# lh.net
KiCad netlist of a schematic drawn in EAGLE
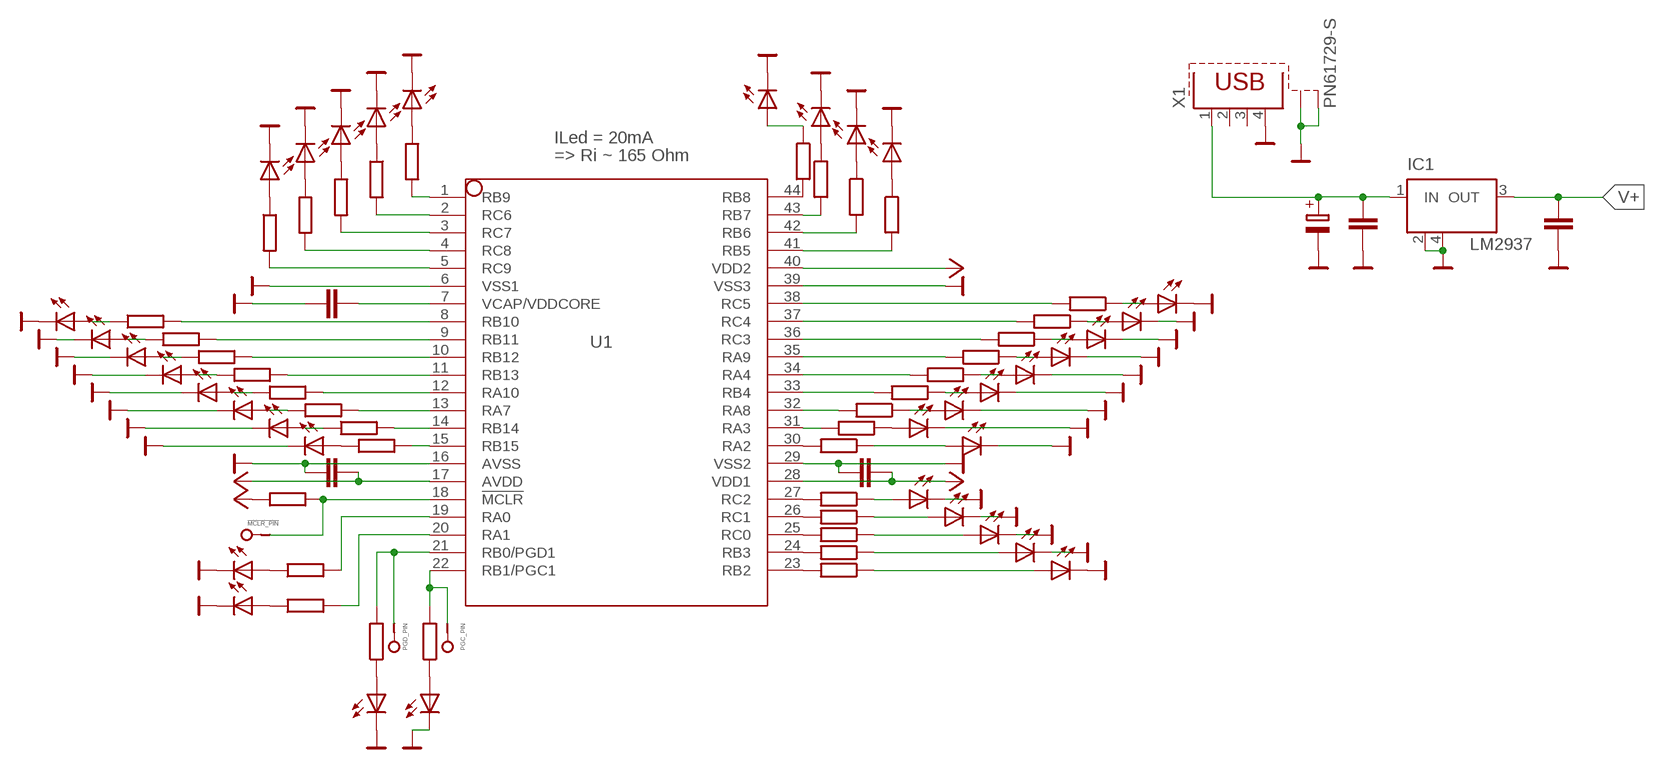
[diagram p0: schematic, sheet 1]

(export (version "E")
  (design (tool "Eeschema 10.0.6"))
  (components
    (comp (ref "!MCLR_PIN")
      (value "1_PIN_CONPLANAR")
      (footprint "eagle-import:1_PIN_PLANAR")
      (libsource (lib "eagle-import") (part "1_PIN_CONPLANAR"))
    )
    (comp (ref "C1")
      (value "SMD_CAPC0805K")
      (footprint "eagle-import:C0805K")
      (libsource (lib "eagle-import") (part "SMD_CAPC0805K"))
    )
    (comp (ref "C2")
      (value "SMD_CAPC0805K")
      (footprint "eagle-import:C0805K")
      (libsource (lib "eagle-import") (part "SMD_CAPC0805K"))
    )
    (comp (ref "C3")
      (value "SMD_CAPC0805K")
      (footprint "eagle-import:C0805K")
      (libsource (lib "eagle-import") (part "SMD_CAPC0805K"))
    )
    (comp (ref "C5")
      (value "SMD_CAPC0805K")
      (footprint "eagle-import:C0805K")
      (libsource (lib "eagle-import") (part "SMD_CAPC0805K"))
    )
    (comp (ref "C6")
      (value "SMD_CAPC0805K")
      (footprint "eagle-import:C0805K")
      (libsource (lib "eagle-import") (part "SMD_CAPC0805K"))
    )
    (comp (ref "C7")
      (value "SMD_EL_CAP")
      (footprint "eagle-import:153CLV-0405")
      (libsource (lib "eagle-import") (part "SMD_EL_CAP"))
    )
    (comp (ref "IC1")
      (value "LM2937")
      (footprint "eagle-import:SOT223")
      (libsource (lib "eagle-import") (part "LM2937"))
    )
    (comp (ref "LED1")
      (value "LEDSMT1206")
      (footprint "eagle-import:1206")
      (libsource (lib "eagle-import") (part "LEDSMT1206"))
    )
    (comp (ref "LED2")
      (value "LEDSMT1206")
      (footprint "eagle-import:1206")
      (libsource (lib "eagle-import") (part "LEDSMT1206"))
    )
    (comp (ref "LED3")
      (value "LEDSMT1206")
      (footprint "eagle-import:1206")
      (libsource (lib "eagle-import") (part "LEDSMT1206"))
    )
    (comp (ref "LED4")
      (value "LEDSMT1206")
      (footprint "eagle-import:1206")
      (libsource (lib "eagle-import") (part "LEDSMT1206"))
    )
    (comp (ref "LED5")
      (value "LEDSMT1206")
      (footprint "eagle-import:1206")
      (libsource (lib "eagle-import") (part "LEDSMT1206"))
    )
    (comp (ref "LED6")
      (value "LEDSMT1206")
      (footprint "eagle-import:1206")
      (libsource (lib "eagle-import") (part "LEDSMT1206"))
    )
    (comp (ref "LED7")
      (value "LEDSMT1206")
      (footprint "eagle-import:1206")
      (libsource (lib "eagle-import") (part "LEDSMT1206"))
    )
    (comp (ref "LED8")
      (value "LEDSMT1206")
      (footprint "eagle-import:1206")
      (libsource (lib "eagle-import") (part "LEDSMT1206"))
    )
    (comp (ref "LED9")
      (value "LEDSMT1206")
      (footprint "eagle-import:1206")
      (libsource (lib "eagle-import") (part "LEDSMT1206"))
    )
    (comp (ref "LED10")
      (value "LEDSMT1206")
      (footprint "eagle-import:1206")
      (libsource (lib "eagle-import") (part "LEDSMT1206"))
    )
    (comp (ref "LED11")
      (value "LEDSMT1206")
      (footprint "eagle-import:1206")
      (libsource (lib "eagle-import") (part "LEDSMT1206"))
    )
    (comp (ref "LED12")
      (value "LEDSMT1206")
      (footprint "eagle-import:1206")
      (libsource (lib "eagle-import") (part "LEDSMT1206"))
    )
    (comp (ref "LED13")
      (value "LEDSMT1206")
      (footprint "eagle-import:1206")
      (libsource (lib "eagle-import") (part "LEDSMT1206"))
    )
    (comp (ref "LED14")
      (value "LEDSMT1206")
      (footprint "eagle-import:1206")
      (libsource (lib "eagle-import") (part "LEDSMT1206"))
    )
    (comp (ref "LED15")
      (value "LEDSMT1206")
      (footprint "eagle-import:1206")
      (libsource (lib "eagle-import") (part "LEDSMT1206"))
    )
    (comp (ref "LED16")
      (value "LEDSMT1206")
      (footprint "eagle-import:1206")
      (libsource (lib "eagle-import") (part "LEDSMT1206"))
    )
    (comp (ref "LED17")
      (value "LEDSMT1206")
      (footprint "eagle-import:1206")
      (libsource (lib "eagle-import") (part "LEDSMT1206"))
    )
    (comp (ref "LED18")
      (value "LEDSMT1206")
      (footprint "eagle-import:1206")
      (libsource (lib "eagle-import") (part "LEDSMT1206"))
    )
    (comp (ref "LED19")
      (value "LEDSMT1206")
      (footprint "eagle-import:1206")
      (libsource (lib "eagle-import") (part "LEDSMT1206"))
    )
    (comp (ref "LED20")
      (value "LEDSMT1206")
      (footprint "eagle-import:1206")
      (libsource (lib "eagle-import") (part "LEDSMT1206"))
    )
    (comp (ref "LED21")
      (value "LEDSMT1206")
      (footprint "eagle-import:1206")
      (libsource (lib "eagle-import") (part "LEDSMT1206"))
    )
    (comp (ref "LED22")
      (value "LEDSMT1206")
      (footprint "eagle-import:1206")
      (libsource (lib "eagle-import") (part "LEDSMT1206"))
    )
    (comp (ref "LED23")
      (value "LEDSMT1206")
      (footprint "eagle-import:1206")
      (libsource (lib "eagle-import") (part "LEDSMT1206"))
    )
    (comp (ref "LED24")
      (value "LEDSMT1206")
      (footprint "eagle-import:1206")
      (libsource (lib "eagle-import") (part "LEDSMT1206"))
    )
    (comp (ref "LED25")
      (value "LEDSMT1206")
      (footprint "eagle-import:1206")
      (libsource (lib "eagle-import") (part "LEDSMT1206"))
    )
    (comp (ref "LED26")
      (value "LEDSMT1206")
      (footprint "eagle-import:1206")
      (libsource (lib "eagle-import") (part "LEDSMT1206"))
    )
    (comp (ref "LED27")
      (value "LEDSMT1206")
      (footprint "eagle-import:1206")
      (libsource (lib "eagle-import") (part "LEDSMT1206"))
    )
    (comp (ref "LED28")
      (value "LEDSMT1206")
      (footprint "eagle-import:1206")
      (libsource (lib "eagle-import") (part "LEDSMT1206"))
    )
    (comp (ref "LED29")
      (value "LEDSMT1206")
      (footprint "eagle-import:1206")
      (libsource (lib "eagle-import") (part "LEDSMT1206"))
    )
    (comp (ref "LED30")
      (value "LEDSMT1206")
      (footprint "eagle-import:1206")
      (libsource (lib "eagle-import") (part "LEDSMT1206"))
    )
    (comp (ref "LED31")
      (value "LEDSMT1206")
      (footprint "eagle-import:1206")
      (libsource (lib "eagle-import") (part "LEDSMT1206"))
    )
    (comp (ref "LED32")
      (value "LEDSMT1206")
      (footprint "eagle-import:1206")
      (libsource (lib "eagle-import") (part "LEDSMT1206"))
    )
    (comp (ref "LED33")
      (value "LEDSMT1206")
      (footprint "eagle-import:1206")
      (libsource (lib "eagle-import") (part "LEDSMT1206"))
    )
    (comp (ref "LED34")
      (value "LEDSMT1206")
      (footprint "eagle-import:1206")
      (libsource (lib "eagle-import") (part "LEDSMT1206"))
    )
    (comp (ref "LED35")
      (value "LEDSMT1206")
      (footprint "eagle-import:1206")
      (libsource (lib "eagle-import") (part "LEDSMT1206"))
    )
    (comp (ref "PGC_PIN")
      (value "1_PIN_CONPLANAR")
      (footprint "eagle-import:1_PIN_PLANAR")
      (libsource (lib "eagle-import") (part "1_PIN_CONPLANAR"))
    )
    (comp (ref "PGD_PIN")
      (value "1_PIN_CONPLANAR")
      (footprint "eagle-import:1_PIN_PLANAR")
      (libsource (lib "eagle-import") (part "1_PIN_CONPLANAR"))
    )
    (comp (ref "R1")
      (value "SMD_RES")
      (footprint "eagle-import:R1206")
      (libsource (lib "eagle-import") (part "SMD_RES"))
    )
    (comp (ref "R2")
      (value "SMD_RES")
      (footprint "eagle-import:R1206")
      (libsource (lib "eagle-import") (part "SMD_RES"))
    )
    (comp (ref "R3")
      (value "SMD_RES")
      (footprint "eagle-import:R1206")
      (libsource (lib "eagle-import") (part "SMD_RES"))
    )
    (comp (ref "R4")
      (value "SMD_RES")
      (footprint "eagle-import:R1206")
      (libsource (lib "eagle-import") (part "SMD_RES"))
    )
    (comp (ref "R5")
      (value "SMD_RES")
      (footprint "eagle-import:R1206")
      (libsource (lib "eagle-import") (part "SMD_RES"))
    )
    (comp (ref "R6")
      (value "SMD_RES")
      (footprint "eagle-import:R1206")
      (libsource (lib "eagle-import") (part "SMD_RES"))
    )
    (comp (ref "R7")
      (value "SMD_RES")
      (footprint "eagle-import:R1206")
      (libsource (lib "eagle-import") (part "SMD_RES"))
    )
    (comp (ref "R8")
      (value "SMD_RES")
      (footprint "eagle-import:R1206")
      (libsource (lib "eagle-import") (part "SMD_RES"))
    )
    (comp (ref "R9")
      (value "SMD_RES")
      (footprint "eagle-import:R1206")
      (libsource (lib "eagle-import") (part "SMD_RES"))
    )
    (comp (ref "R10")
      (value "SMD_RES")
      (footprint "eagle-import:R1206")
      (libsource (lib "eagle-import") (part "SMD_RES"))
    )
    (comp (ref "R11")
      (value "SMD_RES")
      (footprint "eagle-import:R1206")
      (libsource (lib "eagle-import") (part "SMD_RES"))
    )
    (comp (ref "R12")
      (value "SMD_RES")
      (footprint "eagle-import:R1206")
      (libsource (lib "eagle-import") (part "SMD_RES"))
    )
    (comp (ref "R13")
      (value "SMD_RES")
      (footprint "eagle-import:R1206")
      (libsource (lib "eagle-import") (part "SMD_RES"))
    )
    (comp (ref "R14")
      (value "SMD_RES")
      (footprint "eagle-import:R1206")
      (libsource (lib "eagle-import") (part "SMD_RES"))
    )
    (comp (ref "R15")
      (value "SMD_RES")
      (footprint "eagle-import:R1206")
      (libsource (lib "eagle-import") (part "SMD_RES"))
    )
    (comp (ref "R16")
      (value "SMD_RES")
      (footprint "eagle-import:R1206")
      (libsource (lib "eagle-import") (part "SMD_RES"))
    )
    (comp (ref "R17")
      (value "SMD_RES")
      (footprint "eagle-import:R1206")
      (libsource (lib "eagle-import") (part "SMD_RES"))
    )
    (comp (ref "R18")
      (value "SMD_RES")
      (footprint "eagle-import:R1206")
      (libsource (lib "eagle-import") (part "SMD_RES"))
    )
    (comp (ref "R19")
      (value "SMD_RES")
      (footprint "eagle-import:R1206")
      (libsource (lib "eagle-import") (part "SMD_RES"))
    )
    (comp (ref "R20")
      (value "SMD_RES")
      (footprint "eagle-import:R1206")
      (libsource (lib "eagle-import") (part "SMD_RES"))
    )
    (comp (ref "R21")
      (value "SMD_RES")
      (footprint "eagle-import:R1206")
      (libsource (lib "eagle-import") (part "SMD_RES"))
    )
    (comp (ref "R22")
      (value "SMD_RES")
      (footprint "eagle-import:R1206")
      (libsource (lib "eagle-import") (part "SMD_RES"))
    )
    (comp (ref "R23")
      (value "SMD_RES")
      (footprint "eagle-import:R1206")
      (libsource (lib "eagle-import") (part "SMD_RES"))
    )
    (comp (ref "R24")
      (value "SMD_RES")
      (footprint "eagle-import:R1206")
      (libsource (lib "eagle-import") (part "SMD_RES"))
    )
    (comp (ref "R25")
      (value "SMD_RES")
      (footprint "eagle-import:R1206")
      (libsource (lib "eagle-import") (part "SMD_RES"))
    )
    (comp (ref "R26")
      (value "SMD_RES")
      (footprint "eagle-import:R1206")
      (libsource (lib "eagle-import") (part "SMD_RES"))
    )
    (comp (ref "R27")
      (value "SMD_RES")
      (footprint "eagle-import:R1206")
      (libsource (lib "eagle-import") (part "SMD_RES"))
    )
    (comp (ref "R28")
      (value "SMD_RES")
      (footprint "eagle-import:R1206")
      (libsource (lib "eagle-import") (part "SMD_RES"))
    )
    (comp (ref "R29")
      (value "SMD_RES")
      (footprint "eagle-import:R1206")
      (libsource (lib "eagle-import") (part "SMD_RES"))
    )
    (comp (ref "R30")
      (value "SMD_RES")
      (footprint "eagle-import:R1206")
      (libsource (lib "eagle-import") (part "SMD_RES"))
    )
    (comp (ref "R31")
      (value "SMD_RES")
      (footprint "eagle-import:R1206")
      (libsource (lib "eagle-import") (part "SMD_RES"))
    )
    (comp (ref "R32")
      (value "SMD_RES")
      (footprint "eagle-import:R1206")
      (libsource (lib "eagle-import") (part "SMD_RES"))
    )
    (comp (ref "R33")
      (value "SMD_RES")
      (footprint "eagle-import:R1206")
      (libsource (lib "eagle-import") (part "SMD_RES"))
    )
    (comp (ref "R34")
      (value "SMD_RES")
      (footprint "eagle-import:R1206")
      (libsource (lib "eagle-import") (part "SMD_RES"))
    )
    (comp (ref "R35")
      (value "SMD_RES")
      (footprint "eagle-import:R1206")
      (libsource (lib "eagle-import") (part "SMD_RES"))
    )
    (comp (ref "R36")
      (value "SMD_RES")
      (footprint "eagle-import:R1206")
      (libsource (lib "eagle-import") (part "SMD_RES"))
    )
    (comp (ref "U1")
      (value "DSPIC33FJ64GP204")
      (footprint "eagle-import:TQFP44")
      (libsource (lib "eagle-import") (part "DSPIC33FJ64GP204"))
    )
    (comp (ref "X1")
      (value "PN61729-S")
      (footprint "eagle-import:PN61729-S")
      (libsource (lib "eagle-import") (part "PN61729-S"))
    )
  )
  (nets
    (net (code "1") (name "0V") (class "Default")
      (node (ref "C1") (pin "2") (pinfunction "2_2") (pintype "passive"))
      (node (ref "C2") (pin "2") (pinfunction "2_2") (pintype "passive"))
      (node (ref "C3") (pin "1") (pinfunction "1_1") (pintype "passive"))
      (node (ref "C5") (pin "2") (pinfunction "2_2") (pintype "passive"))
      (node (ref "C6") (pin "2") (pinfunction "2_2") (pintype "passive"))
      (node (ref "C7") (pin "-") (pinfunction "P$2_-") (pintype "bidirectional"))
      (node (ref "IC1") (pin "2") (pinfunction "GND_2") (pintype "power_in"))
      (node (ref "IC1") (pin "4") (pinfunction "GND_4") (pintype "power_in"))
      (node (ref "LED1") (pin "C") (pinfunction "C_C") (pintype "passive"))
      (node (ref "LED10") (pin "C") (pinfunction "C_C") (pintype "passive"))
      (node (ref "LED11") (pin "C") (pinfunction "C_C") (pintype "passive"))
      (node (ref "LED12") (pin "C") (pinfunction "C_C") (pintype "passive"))
      (node (ref "LED13") (pin "C") (pinfunction "C_C") (pintype "passive"))
      (node (ref "LED14") (pin "C") (pinfunction "C_C") (pintype "passive"))
      (node (ref "LED15") (pin "C") (pinfunction "C_C") (pintype "passive"))
      (node (ref "LED16") (pin "C") (pinfunction "C_C") (pintype "passive"))
      (node (ref "LED17") (pin "C") (pinfunction "C_C") (pintype "passive"))
      (node (ref "LED18") (pin "C") (pinfunction "C_C") (pintype "passive"))
      (node (ref "LED19") (pin "C") (pinfunction "C_C") (pintype "passive"))
      (node (ref "LED2") (pin "C") (pinfunction "C_C") (pintype "passive"))
      (node (ref "LED20") (pin "C") (pinfunction "C_C") (pintype "passive"))
      (node (ref "LED21") (pin "C") (pinfunction "C_C") (pintype "passive"))
      (node (ref "LED22") (pin "C") (pinfunction "C_C") (pintype "passive"))
      (node (ref "LED23") (pin "C") (pinfunction "C_C") (pintype "passive"))
      (node (ref "LED24") (pin "C") (pinfunction "C_C") (pintype "passive"))
      (node (ref "LED25") (pin "C") (pinfunction "C_C") (pintype "passive"))
      (node (ref "LED26") (pin "C") (pinfunction "C_C") (pintype "passive"))
      (node (ref "LED27") (pin "C") (pinfunction "C_C") (pintype "passive"))
      (node (ref "LED28") (pin "C") (pinfunction "C_C") (pintype "passive"))
      (node (ref "LED29") (pin "C") (pinfunction "C_C") (pintype "passive"))
      (node (ref "LED3") (pin "C") (pinfunction "C_C") (pintype "passive"))
      (node (ref "LED30") (pin "C") (pinfunction "C_C") (pintype "passive"))
      (node (ref "LED31") (pin "C") (pinfunction "C_C") (pintype "passive"))
      (node (ref "LED32") (pin "C") (pinfunction "C_C") (pintype "passive"))
      (node (ref "LED33") (pin "C") (pinfunction "C_C") (pintype "passive"))
      (node (ref "LED34") (pin "C") (pinfunction "C_C") (pintype "passive"))
      (node (ref "LED35") (pin "C") (pinfunction "C_C") (pintype "passive"))
      (node (ref "LED4") (pin "C") (pinfunction "C_C") (pintype "passive"))
      (node (ref "LED5") (pin "C") (pinfunction "C_C") (pintype "passive"))
      (node (ref "LED6") (pin "C") (pinfunction "C_C") (pintype "passive"))
      (node (ref "LED7") (pin "C") (pinfunction "C_C") (pintype "passive"))
      (node (ref "LED8") (pin "C") (pinfunction "C_C") (pintype "passive"))
      (node (ref "LED9") (pin "C") (pinfunction "C_C") (pintype "passive"))
      (node (ref "U1") (pin "16") (pinfunction "AVSS_16") (pintype "bidirectional"))
      (node (ref "U1") (pin "29") (pinfunction "VSS2_29") (pintype "bidirectional"))
      (node (ref "U1") (pin "39") (pinfunction "VSS3_39") (pintype "bidirectional"))
      (node (ref "U1") (pin "6") (pinfunction "VSS1_6") (pintype "bidirectional"))
      (node (ref "X1") (pin "4") (pinfunction "4_4") (pintype "passive"))
      (node (ref "X1") (pin "S1") (pinfunction "S1_S1") (pintype "passive"))
      (node (ref "X1") (pin "S2") (pinfunction "S2_S2") (pintype "passive"))
    )
    (net (code "2") (name "Net-(C7-P$1)") (class "Default")
      (node (ref "C2") (pin "1") (pinfunction "1_1") (pintype "passive"))
      (node (ref "C7") (pin "+") (pinfunction "P$1_+") (pintype "bidirectional"))
      (node (ref "IC1") (pin "1") (pinfunction "IN_1") (pintype "input"))
      (node (ref "X1") (pin "1") (pinfunction "1_1") (pintype "passive"))
    )
    (net (code "3") (name "Net-(LED1-PadA)") (class "Default")
      (node (ref "LED1") (pin "A") (pinfunction "A_A") (pintype "passive"))
      (node (ref "R1") (pin "1") (pinfunction "1_1") (pintype "passive"))
    )
    (net (code "4") (name "Net-(LED2-PadA)") (class "Default")
      (node (ref "LED2") (pin "A") (pinfunction "A_A") (pintype "passive"))
      (node (ref "R2") (pin "1") (pinfunction "1_1") (pintype "passive"))
    )
    (net (code "5") (name "Net-(LED3-PadA)") (class "Default")
      (node (ref "LED3") (pin "A") (pinfunction "A_A") (pintype "passive"))
      (node (ref "R3") (pin "1") (pinfunction "1_1") (pintype "passive"))
    )
    (net (code "6") (name "Net-(LED4-PadA)") (class "Default")
      (node (ref "LED4") (pin "A") (pinfunction "A_A") (pintype "passive"))
      (node (ref "R4") (pin "1") (pinfunction "1_1") (pintype "passive"))
    )
    (net (code "7") (name "Net-(LED5-PadA)") (class "Default")
      (node (ref "LED5") (pin "A") (pinfunction "A_A") (pintype "passive"))
      (node (ref "R5") (pin "1") (pinfunction "1_1") (pintype "passive"))
    )
    (net (code "8") (name "Net-(LED6-PadA)") (class "Default")
      (node (ref "LED6") (pin "A") (pinfunction "A_A") (pintype "passive"))
      (node (ref "R6") (pin "1") (pinfunction "1_1") (pintype "passive"))
    )
    (net (code "9") (name "Net-(LED7-PadA)") (class "Default")
      (node (ref "LED7") (pin "A") (pinfunction "A_A") (pintype "passive"))
      (node (ref "R13") (pin "1") (pinfunction "1_1") (pintype "passive"))
    )
    (net (code "10") (name "Net-(LED8-PadA)") (class "Default")
      (node (ref "LED8") (pin "A") (pinfunction "A_A") (pintype "passive"))
      (node (ref "R14") (pin "1") (pinfunction "1_1") (pintype "passive"))
    )
    (net (code "11") (name "Net-(LED9-PadA)") (class "Default")
      (node (ref "LED9") (pin "A") (pinfunction "A_A") (pintype "passive"))
      (node (ref "R12") (pin "1") (pinfunction "1_1") (pintype "passive"))
    )
    (net (code "12") (name "Net-(LED10-PadA)") (class "Default")
      (node (ref "LED10") (pin "A") (pinfunction "A_A") (pintype "passive"))
      (node (ref "R11") (pin "1") (pinfunction "1_1") (pintype "passive"))
    )
    (net (code "13") (name "Net-(LED11-PadA)") (class "Default")
      (node (ref "LED11") (pin "A") (pinfunction "A_A") (pintype "passive"))
      (node (ref "R10") (pin "1") (pinfunction "1_1") (pintype "passive"))
    )
    (net (code "14") (name "Net-(LED12-PadA)") (class "Default")
      (node (ref "LED12") (pin "A") (pinfunction "A_A") (pintype "passive"))
      (node (ref "R9") (pin "1") (pinfunction "1_1") (pintype "passive"))
    )
    (net (code "15") (name "Net-(LED13-PadA)") (class "Default")
      (node (ref "LED13") (pin "A") (pinfunction "A_A") (pintype "passive"))
      (node (ref "R8") (pin "1") (pinfunction "1_1") (pintype "passive"))
    )
    (net (code "16") (name "Net-(LED14-PadA)") (class "Default")
      (node (ref "LED14") (pin "A") (pinfunction "A_A") (pintype "passive"))
      (node (ref "R7") (pin "1") (pinfunction "1_1") (pintype "passive"))
    )
    (net (code "17") (name "Net-(LED15-PadA)") (class "Default")
      (node (ref "LED15") (pin "A") (pinfunction "A_A") (pintype "passive"))
      (node (ref "R16") (pin "1") (pinfunction "1_1") (pintype "passive"))
    )
    (net (code "18") (name "Net-(LED16-PadA)") (class "Default")
      (node (ref "LED16") (pin "A") (pinfunction "A_A") (pintype "passive"))
      (node (ref "R17") (pin "1") (pinfunction "1_1") (pintype "passive"))
    )
    (net (code "19") (name "Net-(LED17-PadA)") (class "Default")
      (node (ref "LED17") (pin "A") (pinfunction "A_A") (pintype "passive"))
      (node (ref "R18") (pin "1") (pinfunction "1_1") (pintype "passive"))
    )
    (net (code "20") (name "Net-(LED18-PadA)") (class "Default")
      (node (ref "LED18") (pin "A") (pinfunction "A_A") (pintype "passive"))
      (node (ref "R19") (pin "1") (pinfunction "1_1") (pintype "passive"))
    )
    (net (code "21") (name "Net-(LED19-PadA)") (class "Default")
      (node (ref "LED19") (pin "A") (pinfunction "A_A") (pintype "passive"))
      (node (ref "R20") (pin "1") (pinfunction "1_1") (pintype "passive"))
    )
    (net (code "22") (name "Net-(LED20-PadA)") (class "Default")
      (node (ref "LED20") (pin "A") (pinfunction "A_A") (pintype "passive"))
      (node (ref "R21") (pin "1") (pinfunction "1_1") (pintype "passive"))
    )
    (net (code "23") (name "Net-(LED21-PadA)") (class "Default")
      (node (ref "LED21") (pin "A") (pinfunction "A_A") (pintype "passive"))
      (node (ref "R22") (pin "1") (pinfunction "1_1") (pintype "passive"))
    )
    (net (code "24") (name "Net-(LED22-PadA)") (class "Default")
      (node (ref "LED22") (pin "A") (pinfunction "A_A") (pintype "passive"))
      (node (ref "R29") (pin "1") (pinfunction "1_1") (pintype "passive"))
    )
    (net (code "25") (name "Net-(LED23-PadA)") (class "Default")
      (node (ref "LED23") (pin "A") (pinfunction "A_A") (pintype "passive"))
      (node (ref "R30") (pin "1") (pinfunction "1_1") (pintype "passive"))
    )
    (net (code "26") (name "Net-(LED24-PadA)") (class "Default")
      (node (ref "LED24") (pin "A") (pinfunction "A_A") (pintype "passive"))
      (node (ref "R28") (pin "1") (pinfunction "1_1") (pintype "passive"))
    )
    (net (code "27") (name "Net-(LED25-PadA)") (class "Default")
      (node (ref "LED25") (pin "A") (pinfunction "A_A") (pintype "passive"))
      (node (ref "R27") (pin "1") (pinfunction "1_1") (pintype "passive"))
    )
    (net (code "28") (name "Net-(LED26-PadA)") (class "Default")
      (node (ref "LED26") (pin "A") (pinfunction "A_A") (pintype "passive"))
      (node (ref "R26") (pin "1") (pinfunction "1_1") (pintype "passive"))
    )
    (net (code "29") (name "Net-(LED27-PadA)") (class "Default")
      (node (ref "LED27") (pin "A") (pinfunction "A_A") (pintype "passive"))
      (node (ref "R25") (pin "1") (pinfunction "1_1") (pintype "passive"))
    )
    (net (code "30") (name "Net-(LED28-PadA)") (class "Default")
      (node (ref "LED28") (pin "A") (pinfunction "A_A") (pintype "passive"))
      (node (ref "R24") (pin "1") (pinfunction "1_1") (pintype "passive"))
    )
    (net (code "31") (name "Net-(LED29-PadA)") (class "Default")
      (node (ref "LED29") (pin "A") (pinfunction "A_A") (pintype "passive"))
      (node (ref "R23") (pin "1") (pinfunction "1_1") (pintype "passive"))
    )
    (net (code "32") (name "Net-(LED30-PadA)") (class "Default")
      (node (ref "LED30") (pin "A") (pinfunction "A_A") (pintype "passive"))
      (node (ref "R31") (pin "1") (pinfunction "1_1") (pintype "passive"))
    )
    (net (code "33") (name "Net-(LED31-PadA)") (class "Default")
      (node (ref "LED31") (pin "A") (pinfunction "A_A") (pintype "passive"))
      (node (ref "R36") (pin "1") (pinfunction "1_1") (pintype "passive"))
    )
    (net (code "34") (name "Net-(LED32-PadA)") (class "Default")
      (node (ref "LED32") (pin "A") (pinfunction "A_A") (pintype "passive"))
      (node (ref "R35") (pin "1") (pinfunction "1_1") (pintype "passive"))
    )
    (net (code "35") (name "Net-(LED33-PadA)") (class "Default")
      (node (ref "LED33") (pin "A") (pinfunction "A_A") (pintype "passive"))
      (node (ref "R34") (pin "1") (pinfunction "1_1") (pintype "passive"))
    )
    (net (code "36") (name "Net-(LED34-PadA)") (class "Default")
      (node (ref "LED34") (pin "A") (pinfunction "A_A") (pintype "passive"))
      (node (ref "R33") (pin "1") (pinfunction "1_1") (pintype "passive"))
    )
    (net (code "37") (name "Net-(LED35-PadA)") (class "Default")
      (node (ref "LED35") (pin "A") (pinfunction "A_A") (pintype "passive"))
      (node (ref "R32") (pin "1") (pinfunction "1_1") (pintype "passive"))
    )
    (net (code "38") (name "Net-(U1-RA0)") (class "Default")
      (node (ref "R16") (pin "2") (pinfunction "2_2") (pintype "passive"))
      (node (ref "U1") (pin "19") (pinfunction "RA0_19") (pintype "bidirectional"))
    )
    (net (code "39") (name "Net-(U1-RA1)") (class "Default")
      (node (ref "R17") (pin "2") (pinfunction "2_2") (pintype "passive"))
      (node (ref "U1") (pin "20") (pinfunction "RA1_20") (pintype "bidirectional"))
    )
    (net (code "40") (name "Net-(U1-RA2)") (class "Default")
      (node (ref "R31") (pin "2") (pinfunction "2_2") (pintype "passive"))
      (node (ref "U1") (pin "30") (pinfunction "RA2_30") (pintype "bidirectional"))
    )
    (net (code "41") (name "Net-(U1-RA3)") (class "Default")
      (node (ref "R30") (pin "2") (pinfunction "2_2") (pintype "passive"))
      (node (ref "U1") (pin "31") (pinfunction "RA3_31") (pintype "bidirectional"))
    )
    (net (code "42") (name "Net-(U1-RA4)") (class "Default")
      (node (ref "R27") (pin "2") (pinfunction "2_2") (pintype "passive"))
      (node (ref "U1") (pin "34") (pinfunction "RA4_34") (pintype "bidirectional"))
    )
    (net (code "43") (name "Net-(U1-RA7)") (class "Default")
      (node (ref "R12") (pin "2") (pinfunction "2_2") (pintype "passive"))
      (node (ref "U1") (pin "13") (pinfunction "RA7_13") (pintype "bidirectional"))
    )
    (net (code "44") (name "Net-(U1-RA8)") (class "Default")
      (node (ref "R29") (pin "2") (pinfunction "2_2") (pintype "passive"))
      (node (ref "U1") (pin "32") (pinfunction "RA8_32") (pintype "bidirectional"))
    )
    (net (code "45") (name "Net-(U1-RA9)") (class "Default")
      (node (ref "R26") (pin "2") (pinfunction "2_2") (pintype "passive"))
      (node (ref "U1") (pin "35") (pinfunction "RA9_35") (pintype "bidirectional"))
    )
    (net (code "46") (name "Net-(U1-RA10)") (class "Default")
      (node (ref "R11") (pin "2") (pinfunction "2_2") (pintype "passive"))
      (node (ref "U1") (pin "12") (pinfunction "RA10_12") (pintype "bidirectional"))
    )
    (net (code "47") (name "Net-(U1-RB0{slash}PGD1)") (class "Default")
      (node (ref "PGD_PIN") (pin "P$1") (pinfunction "P$1_P$1") (pintype "bidirectional"))
      (node (ref "R18") (pin "2") (pinfunction "2_2") (pintype "passive"))
      (node (ref "U1") (pin "21") (pinfunction "RB0/PGD1_21") (pintype "bidirectional"))
    )
    (net (code "48") (name "Net-(U1-RB1{slash}PGC1)") (class "Default")
      (node (ref "PGC_PIN") (pin "P$1") (pinfunction "P$1_P$1") (pintype "bidirectional"))
      (node (ref "R19") (pin "2") (pinfunction "2_2") (pintype "passive"))
      (node (ref "U1") (pin "22") (pinfunction "RB1/PGC1_22") (pintype "bidirectional"))
    )
    (net (code "49") (name "Net-(U1-RB2)") (class "Default")
      (node (ref "R36") (pin "2") (pinfunction "2_2") (pintype "passive"))
      (node (ref "U1") (pin "23") (pinfunction "RB2_23") (pintype "bidirectional"))
    )
    (net (code "50") (name "Net-(U1-RB3)") (class "Default")
      (node (ref "R35") (pin "2") (pinfunction "2_2") (pintype "passive"))
      (node (ref "U1") (pin "24") (pinfunction "RB3_24") (pintype "bidirectional"))
    )
    (net (code "51") (name "Net-(U1-RB4)") (class "Default")
      (node (ref "R28") (pin "2") (pinfunction "2_2") (pintype "passive"))
      (node (ref "U1") (pin "33") (pinfunction "RB4_33") (pintype "bidirectional"))
    )
    (net (code "52") (name "Net-(U1-RB5)") (class "Default")
      (node (ref "R22") (pin "2") (pinfunction "2_2") (pintype "passive"))
      (node (ref "U1") (pin "41") (pinfunction "RB5_41") (pintype "bidirectional"))
    )
    (net (code "53") (name "Net-(U1-RB6)") (class "Default")
      (node (ref "R21") (pin "2") (pinfunction "2_2") (pintype "passive"))
      (node (ref "U1") (pin "42") (pinfunction "RB6_42") (pintype "bidirectional"))
    )
    (net (code "54") (name "Net-(U1-RB7)") (class "Default")
      (node (ref "R20") (pin "2") (pinfunction "2_2") (pintype "passive"))
      (node (ref "U1") (pin "43") (pinfunction "RB7_43") (pintype "bidirectional"))
    )
    (net (code "55") (name "Net-(U1-RB8)") (class "Default")
      (node (ref "R6") (pin "2") (pinfunction "2_2") (pintype "passive"))
      (node (ref "U1") (pin "44") (pinfunction "RB8_44") (pintype "bidirectional"))
    )
    (net (code "56") (name "Net-(U1-RB9)") (class "Default")
      (node (ref "R1") (pin "2") (pinfunction "2_2") (pintype "passive"))
      (node (ref "U1") (pin "1") (pinfunction "RB9_1") (pintype "bidirectional"))
    )
    (net (code "57") (name "Net-(U1-RB10)") (class "Default")
      (node (ref "R7") (pin "2") (pinfunction "2_2") (pintype "passive"))
      (node (ref "U1") (pin "8") (pinfunction "RB10_8") (pintype "bidirectional"))
    )
    (net (code "58") (name "Net-(U1-RB11)") (class "Default")
      (node (ref "R8") (pin "2") (pinfunction "2_2") (pintype "passive"))
      (node (ref "U1") (pin "9") (pinfunction "RB11_9") (pintype "bidirectional"))
    )
    (net (code "59") (name "Net-(U1-RB12)") (class "Default")
      (node (ref "R9") (pin "2") (pinfunction "2_2") (pintype "passive"))
      (node (ref "U1") (pin "10") (pinfunction "RB12_10") (pintype "bidirectional"))
    )
    (net (code "60") (name "Net-(U1-RB13)") (class "Default")
      (node (ref "R10") (pin "2") (pinfunction "2_2") (pintype "passive"))
      (node (ref "U1") (pin "11") (pinfunction "RB13_11") (pintype "bidirectional"))
    )
    (net (code "61") (name "Net-(U1-RB14)") (class "Default")
      (node (ref "R13") (pin "2") (pinfunction "2_2") (pintype "passive"))
      (node (ref "U1") (pin "14") (pinfunction "RB14_14") (pintype "bidirectional"))
    )
    (net (code "62") (name "Net-(U1-RB15)") (class "Default")
      (node (ref "R14") (pin "2") (pinfunction "2_2") (pintype "passive"))
      (node (ref "U1") (pin "15") (pinfunction "RB15_15") (pintype "bidirectional"))
    )
    (net (code "63") (name "Net-(U1-RC0)") (class "Default")
      (node (ref "R34") (pin "2") (pinfunction "2_2") (pintype "passive"))
      (node (ref "U1") (pin "25") (pinfunction "RC0_25") (pintype "bidirectional"))
    )
    (net (code "64") (name "Net-(U1-RC1)") (class "Default")
      (node (ref "R33") (pin "2") (pinfunction "2_2") (pintype "passive"))
      (node (ref "U1") (pin "26") (pinfunction "RC1_26") (pintype "bidirectional"))
    )
    (net (code "65") (name "Net-(U1-RC2)") (class "Default")
      (node (ref "R32") (pin "2") (pinfunction "2_2") (pintype "passive"))
      (node (ref "U1") (pin "27") (pinfunction "RC2_27") (pintype "bidirectional"))
    )
    (net (code "66") (name "Net-(U1-RC3)") (class "Default")
      (node (ref "R25") (pin "2") (pinfunction "2_2") (pintype "passive"))
      (node (ref "U1") (pin "36") (pinfunction "RC3_36") (pintype "bidirectional"))
    )
    (net (code "67") (name "Net-(U1-RC4)") (class "Default")
      (node (ref "R24") (pin "2") (pinfunction "2_2") (pintype "passive"))
      (node (ref "U1") (pin "37") (pinfunction "RC4_37") (pintype "bidirectional"))
    )
    (net (code "68") (name "Net-(U1-RC5)") (class "Default")
      (node (ref "R23") (pin "2") (pinfunction "2_2") (pintype "passive"))
      (node (ref "U1") (pin "38") (pinfunction "RC5_38") (pintype "bidirectional"))
    )
    (net (code "69") (name "Net-(U1-RC6)") (class "Default")
      (node (ref "R2") (pin "2") (pinfunction "2_2") (pintype "passive"))
      (node (ref "U1") (pin "2") (pinfunction "RC6_2") (pintype "bidirectional"))
    )
    (net (code "70") (name "Net-(U1-RC7)") (class "Default")
      (node (ref "R3") (pin "2") (pinfunction "2_2") (pintype "passive"))
      (node (ref "U1") (pin "3") (pinfunction "RC7_3") (pintype "bidirectional"))
    )
    (net (code "71") (name "Net-(U1-RC8)") (class "Default")
      (node (ref "R4") (pin "2") (pinfunction "2_2") (pintype "passive"))
      (node (ref "U1") (pin "4") (pinfunction "RC8_4") (pintype "bidirectional"))
    )
    (net (code "72") (name "Net-(U1-RC9)") (class "Default")
      (node (ref "R5") (pin "2") (pinfunction "2_2") (pintype "passive"))
      (node (ref "U1") (pin "5") (pinfunction "RC9_5") (pintype "bidirectional"))
    )
    (net (code "73") (name "Net-(U1-VCAP{slash}VDDCORE)") (class "Default")
      (node (ref "C1") (pin "1") (pinfunction "1_1") (pintype "passive"))
      (node (ref "U1") (pin "7") (pinfunction "VCAP/VDDCORE_7") (pintype "bidirectional"))
    )
    (net (code "74") (name "Net-(U1-~{MCLR})") (class "Default")
      (node (ref "!MCLR_PIN") (pin "P$1") (pinfunction "P$1_P$1") (pintype "bidirectional"))
      (node (ref "R15") (pin "2") (pinfunction "2_2") (pintype "passive"))
      (node (ref "U1") (pin "18") (pinfunction "~{MCLR}_18") (pintype "bidirectional"))
    )
    (net (code "75") (name "V+") (class "Default")
      (node (ref "C3") (pin "2") (pinfunction "2_2") (pintype "passive"))
      (node (ref "C5") (pin "1") (pinfunction "1_1") (pintype "passive"))
      (node (ref "C6") (pin "1") (pinfunction "1_1") (pintype "passive"))
      (node (ref "IC1") (pin "3") (pinfunction "OUT_3") (pintype "passive"))
      (node (ref "R15") (pin "1") (pinfunction "1_1") (pintype "passive"))
      (node (ref "U1") (pin "17") (pinfunction "AVDD_17") (pintype "bidirectional"))
      (node (ref "U1") (pin "28") (pinfunction "VDD1_28") (pintype "bidirectional"))
      (node (ref "U1") (pin "40") (pinfunction "VDD2_40") (pintype "bidirectional"))
    )
    (net (code "76") (name "unconnected-(X1-Pad2)") (class "Default")
      (node (ref "X1") (pin "2") (pinfunction "2_2") (pintype "passive"))
    )
    (net (code "77") (name "unconnected-(X1-Pad3)") (class "Default")
      (node (ref "X1") (pin "3") (pinfunction "3_3") (pintype "passive"))
    )
  )
)
